# Schaltplan.net
KiCad netlist of a schematic drawn in EAGLE
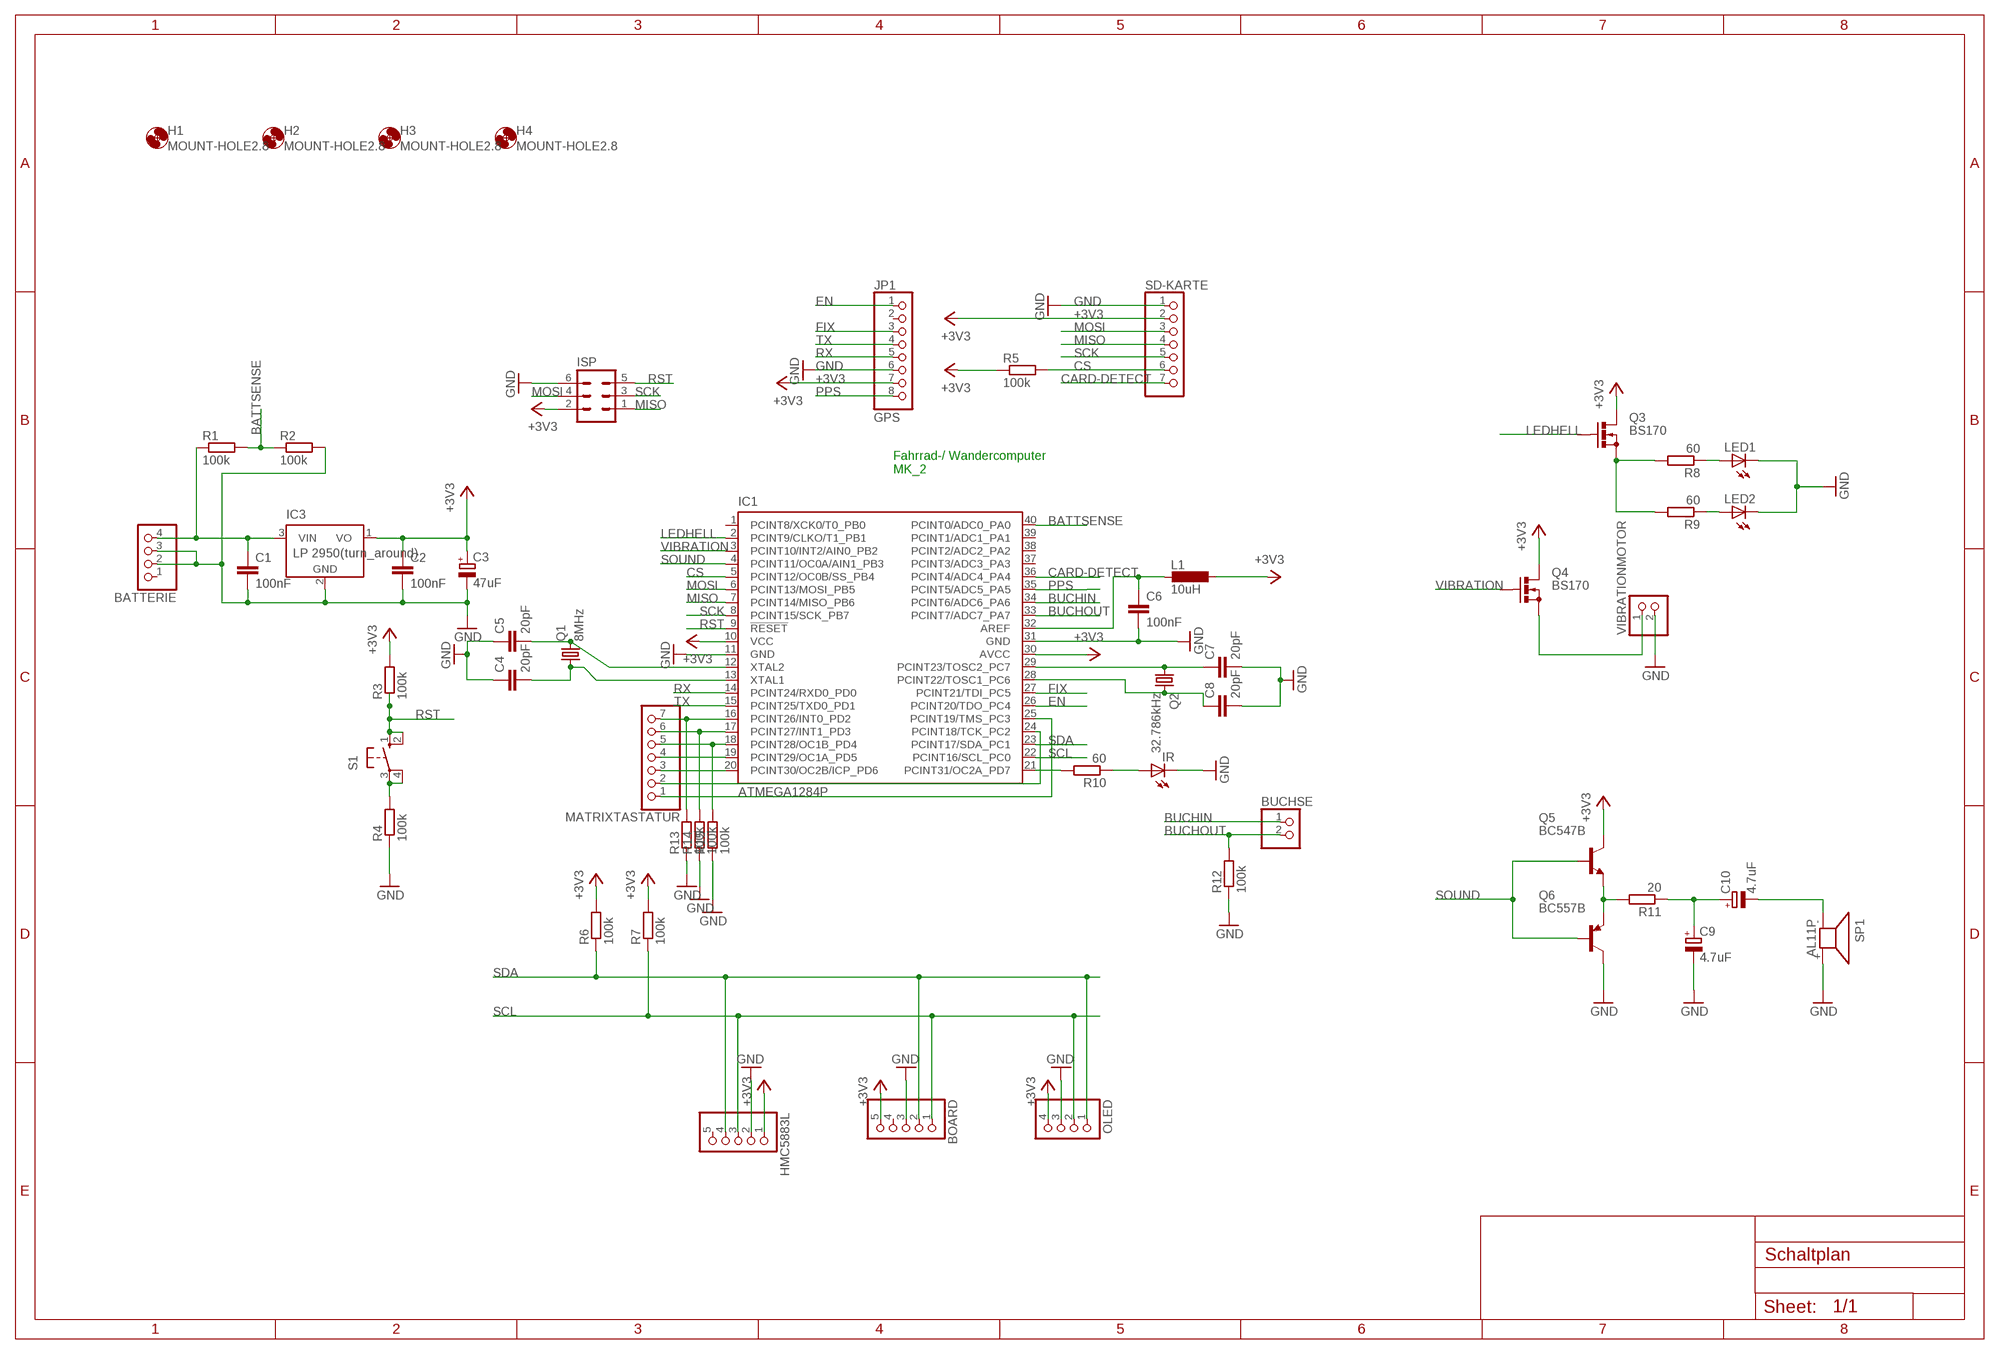
[diagram p0: schematic, sheet 1]

(export (version "E")
  (design (tool "Eeschema 10.0.6"))
  (components
    (comp (ref "BATTERIE")
      (value "PINHD-1X4")
      (footprint "eagle-import:1X04")
      (libsource (lib "eagle-import") (part "PINHD-1X4"))
    )
    (comp (ref "BOARD")
      (value "PINHD-1X5")
      (footprint "eagle-import:1X05")
      (libsource (lib "eagle-import") (part "PINHD-1X5"))
    )
    (comp (ref "BUCHSE")
      (value "PINHD-1X2")
      (footprint "eagle-import:1X02")
      (libsource (lib "eagle-import") (part "PINHD-1X2"))
    )
    (comp (ref "C1")
      (value "100nF")
      (footprint "eagle-import:C025-024X044")
      (libsource (lib "eagle-import") (part "C-EU025-024X044"))
    )
    (comp (ref "C2")
      (value "100nF")
      (footprint "eagle-import:C025-024X044")
      (libsource (lib "eagle-import") (part "C-EU025-024X044"))
    )
    (comp (ref "C3")
      (value "47uF")
      (footprint "eagle-import:E2,5-6")
      (libsource (lib "eagle-import") (part "CPOL-EUE2.5-6"))
    )
    (comp (ref "C4")
      (value "20pF")
      (footprint "eagle-import:C025-024X044")
      (libsource (lib "eagle-import") (part "C-EU025-024X044"))
    )
    (comp (ref "C5")
      (value "20pF")
      (footprint "eagle-import:C025-024X044")
      (libsource (lib "eagle-import") (part "C-EU025-024X044"))
    )
    (comp (ref "C6")
      (value "100nF")
      (footprint "eagle-import:C025-024X044")
      (libsource (lib "eagle-import") (part "C-EU025-024X044"))
    )
    (comp (ref "C7")
      (value "20pF")
      (footprint "eagle-import:C025-024X044")
      (libsource (lib "eagle-import") (part "C-EU025-024X044"))
    )
    (comp (ref "C8")
      (value "20pF")
      (footprint "eagle-import:C025-024X044")
      (libsource (lib "eagle-import") (part "C-EU025-024X044"))
    )
    (comp (ref "C9")
      (value "4.7uF")
      (footprint "eagle-import:E2,5-6")
      (libsource (lib "eagle-import") (part "CPOL-EUE2.5-6"))
    )
    (comp (ref "C10")
      (value "4.7uF")
      (footprint "eagle-import:E2,5-6")
      (libsource (lib "eagle-import") (part "CPOL-EUE2.5-6"))
    )
    (comp (ref "H1")
      (value "MOUNT-HOLE2.8")
      (footprint "eagle-import:2,8")
      (libsource (lib "eagle-import") (part "MOUNT-HOLE2.8"))
    )
    (comp (ref "H2")
      (value "MOUNT-HOLE2.8")
      (footprint "eagle-import:2,8")
      (libsource (lib "eagle-import") (part "MOUNT-HOLE2.8"))
    )
    (comp (ref "H3")
      (value "MOUNT-HOLE2.8")
      (footprint "eagle-import:2,8")
      (libsource (lib "eagle-import") (part "MOUNT-HOLE2.8"))
    )
    (comp (ref "H4")
      (value "MOUNT-HOLE2.8")
      (footprint "eagle-import:2,8")
      (libsource (lib "eagle-import") (part "MOUNT-HOLE2.8"))
    )
    (comp (ref "HMC5883L")
      (value "PINHD-1X5")
      (footprint "eagle-import:1X05")
      (libsource (lib "eagle-import") (part "PINHD-1X5"))
    )
    (comp (ref "IC1")
      (value "ATMEGA1284P")
      (footprint "eagle-import:DIL40")
      (fields (field (name "MPN") "ATMEGA644-20PU"))
      (libsource (lib "eagle-import") (part "ATMEGA644-PU20"))
    )
    (comp (ref "IC3")
      (value "LP 2950(turn_around)")
      (footprint "eagle-import:TO92")
      (fields (field (name "MF") "NATIONAL SEMICONDUCTOR") (field (name "MPN") "LM2936Z-3.0/NOPB"))
      (libsource (lib "eagle-import") (part "LM2936?Z-3.0"))
    )
    (comp (ref "IR")
      (value "LED3MM")
      (footprint "eagle-import:LED3MM")
      (libsource (lib "eagle-import") (part "LED3MM"))
    )
    (comp (ref "ISP")
      (value "ML6")
      (footprint "eagle-import:ML6")
      (libsource (lib "eagle-import") (part "ML6"))
    )
    (comp (ref "JP1")
      (value "GPS")
      (footprint "eagle-import:1X08")
      (libsource (lib "eagle-import") (part "PINHD-1X8"))
    )
    (comp (ref "L1")
      (value "10uH")
      (footprint "eagle-import:0207_10")
      (libsource (lib "eagle-import") (part "L-EU0207/10"))
    )
    (comp (ref "LED1")
      (value "LED5MM")
      (footprint "eagle-import:LED5MM")
      (libsource (lib "eagle-import") (part "LED5MM"))
    )
    (comp (ref "LED2")
      (value "LED5MM")
      (footprint "eagle-import:LED5MM")
      (libsource (lib "eagle-import") (part "LED5MM"))
    )
    (comp (ref "MATRIXTASTATUR")
      (value "PINHD-1X7")
      (footprint "eagle-import:1X07")
      (libsource (lib "eagle-import") (part "PINHD-1X7"))
    )
    (comp (ref "OLED")
      (value "PINHD-1X4")
      (footprint "eagle-import:1X04")
      (libsource (lib "eagle-import") (part "PINHD-1X4"))
    )
    (comp (ref "Q1")
      (value "8MHz")
      (footprint "eagle-import:HC49_S")
      (libsource (lib "eagle-import") (part "CRYSTALHC49S"))
    )
    (comp (ref "Q2")
      (value "32.786kHz")
      (footprint "eagle-import:TC26V")
      (libsource (lib "eagle-import") (part "CRYSTALTC26V"))
    )
    (comp (ref "Q3")
      (value "BS170")
      (footprint "eagle-import:SOT54E")
      (libsource (lib "eagle-import") (part "BS170"))
    )
    (comp (ref "Q4")
      (value "BS170")
      (footprint "eagle-import:SOT54E")
      (libsource (lib "eagle-import") (part "BS170"))
    )
    (comp (ref "Q5")
      (value "BC547B")
      (footprint "eagle-import:TO92")
      (libsource (lib "eagle-import") (part "BC547B"))
    )
    (comp (ref "Q6")
      (value "BC557B")
      (footprint "eagle-import:TO92-EBC")
      (libsource (lib "eagle-import") (part "BC557B"))
    )
    (comp (ref "R1")
      (value "100k")
      (footprint "eagle-import:0207_10")
      (libsource (lib "eagle-import") (part "R-EU_0207/10"))
    )
    (comp (ref "R2")
      (value "100k")
      (footprint "eagle-import:0207_10")
      (libsource (lib "eagle-import") (part "R-EU_0207/10"))
    )
    (comp (ref "R3")
      (value "100k")
      (footprint "eagle-import:0207_10")
      (libsource (lib "eagle-import") (part "R-EU_0207/10"))
    )
    (comp (ref "R4")
      (value "100k")
      (footprint "eagle-import:0207_10")
      (libsource (lib "eagle-import") (part "R-EU_0207/10"))
    )
    (comp (ref "R5")
      (value "100k")
      (footprint "eagle-import:0207_10")
      (libsource (lib "eagle-import") (part "R-EU_0207/10"))
    )
    (comp (ref "R6")
      (value "100k")
      (footprint "eagle-import:0207_10")
      (libsource (lib "eagle-import") (part "R-EU_0207/10"))
    )
    (comp (ref "R7")
      (value "100k")
      (footprint "eagle-import:0207_10")
      (libsource (lib "eagle-import") (part "R-EU_0207/10"))
    )
    (comp (ref "R8")
      (value "60")
      (footprint "eagle-import:0207_10")
      (libsource (lib "eagle-import") (part "R-EU_0207/10"))
    )
    (comp (ref "R9")
      (value "60")
      (footprint "eagle-import:0207_10")
      (libsource (lib "eagle-import") (part "R-EU_0207/10"))
    )
    (comp (ref "R10")
      (value "60")
      (footprint "eagle-import:0207_10")
      (libsource (lib "eagle-import") (part "R-EU_0207/10"))
    )
    (comp (ref "R11")
      (value "20")
      (footprint "eagle-import:0207_10")
      (libsource (lib "eagle-import") (part "R-EU_0207/10"))
    )
    (comp (ref "R12")
      (value "100k")
      (footprint "eagle-import:0207_10")
      (libsource (lib "eagle-import") (part "R-EU_0207/10"))
    )
    (comp (ref "R13")
      (value "100k")
      (footprint "eagle-import:0207_10")
      (libsource (lib "eagle-import") (part "R-EU_0207/10"))
    )
    (comp (ref "R14")
      (value "100k")
      (footprint "eagle-import:0207_10")
      (libsource (lib "eagle-import") (part "R-EU_0207/10"))
    )
    (comp (ref "R15")
      (value "100k")
      (footprint "eagle-import:0207_10")
      (libsource (lib "eagle-import") (part "R-EU_0207/10"))
    )
    (comp (ref "S1")
      (value "10-XX")
      (footprint "eagle-import:B3F-10XX")
      (fields (field (name "MPN") "B3F-1000"))
      (libsource (lib "eagle-import") (part "10-XX"))
    )
    (comp (ref "SD-KARTE")
      (value "PINHD-1X7")
      (footprint "eagle-import:1X07")
      (libsource (lib "eagle-import") (part "PINHD-1X7"))
    )
    (comp (ref "SP1")
      (value "AL11P")
      (footprint "eagle-import:AL11P")
      (libsource (lib "eagle-import") (part "AL11P"))
    )
    (comp (ref "VIBRATIONMOTOR")
      (value "PINHD-1X2")
      (footprint "eagle-import:1X02")
      (libsource (lib "eagle-import") (part "PINHD-1X2"))
    )
  )
  (nets
    (net (code "1") (name "+3V3") (class "Default")
      (node (ref "BOARD") (pin "5") (pinfunction "5_5") (pintype "passive"))
      (node (ref "C2") (pin "1") (pinfunction "1_1") (pintype "passive"))
      (node (ref "C3") (pin "+") (pinfunction "+_+") (pintype "passive"))
      (node (ref "HMC5883L") (pin "1") (pinfunction "1_1") (pintype "passive"))
      (node (ref "IC1") (pin "10") (pinfunction "VCC_10") (pintype "power_in"))
      (node (ref "IC1") (pin "30") (pinfunction "AVCC_30") (pintype "power_in"))
      (node (ref "IC3") (pin "1") (pinfunction "VO_1") (pintype "passive"))
      (node (ref "ISP") (pin "2") (pinfunction "2_2") (pintype "passive"))
      (node (ref "JP1") (pin "7") (pinfunction "7_7") (pintype "passive"))
      (node (ref "L1") (pin "1") (pinfunction "1_1") (pintype "passive"))
      (node (ref "OLED") (pin "4") (pinfunction "4_4") (pintype "passive"))
      (node (ref "Q3") (pin "D") (pinfunction "D_D") (pintype "passive"))
      (node (ref "Q4") (pin "D") (pinfunction "D_D") (pintype "passive"))
      (node (ref "Q5") (pin "3") (pinfunction "C_3") (pintype "passive"))
      (node (ref "R3") (pin "2") (pinfunction "2_2") (pintype "passive"))
      (node (ref "R5") (pin "1") (pinfunction "1_1") (pintype "passive"))
      (node (ref "R6") (pin "2") (pinfunction "2_2") (pintype "passive"))
      (node (ref "R7") (pin "2") (pinfunction "2_2") (pintype "passive"))
      (node (ref "SD-KARTE") (pin "2") (pinfunction "2_2") (pintype "passive"))
    )
    (net (code "2") (name "/BATTSENSE") (class "Default")
      (node (ref "IC1") (pin "40") (pinfunction "PCINT0/ADC0_PA0_40") (pintype "bidirectional"))
      (node (ref "R1") (pin "2") (pinfunction "2_2") (pintype "passive"))
      (node (ref "R2") (pin "1") (pinfunction "1_1") (pintype "passive"))
    )
    (net (code "3") (name "/BUCHIN") (class "Default")
      (node (ref "BUCHSE") (pin "1") (pinfunction "1_1") (pintype "passive"))
      (node (ref "IC1") (pin "34") (pinfunction "PCINT6/ADC6_PA6_34") (pintype "bidirectional"))
    )
    (net (code "4") (name "/BUCHOUT") (class "Default")
      (node (ref "BUCHSE") (pin "2") (pinfunction "2_2") (pintype "passive"))
      (node (ref "IC1") (pin "33") (pinfunction "PCINT7/ADC7_PA7_33") (pintype "bidirectional"))
      (node (ref "R12") (pin "2") (pinfunction "2_2") (pintype "passive"))
    )
    (net (code "5") (name "/CARD-DETECT") (class "Default")
      (node (ref "IC1") (pin "36") (pinfunction "PCINT4/ADC4_PA4_36") (pintype "bidirectional"))
      (node (ref "SD-KARTE") (pin "7") (pinfunction "7_7") (pintype "passive"))
    )
    (net (code "6") (name "/CS") (class "Default")
      (node (ref "IC1") (pin "5") (pinfunction "PCINT12/OC0B/SS_PB4_5") (pintype "bidirectional"))
      (node (ref "R5") (pin "2") (pinfunction "2_2") (pintype "passive"))
      (node (ref "SD-KARTE") (pin "6") (pinfunction "6_6") (pintype "passive"))
    )
    (net (code "7") (name "/EN") (class "Default")
      (node (ref "IC1") (pin "26") (pinfunction "PCINT20/TDO_PC4_26") (pintype "bidirectional"))
      (node (ref "JP1") (pin "1") (pinfunction "1_1") (pintype "passive"))
    )
    (net (code "8") (name "/FIX") (class "Default")
      (node (ref "IC1") (pin "27") (pinfunction "PCINT21/TDI_PC5_27") (pintype "bidirectional"))
      (node (ref "JP1") (pin "3") (pinfunction "3_3") (pintype "passive"))
    )
    (net (code "9") (name "/LEDHELL") (class "Default")
      (node (ref "IC1") (pin "2") (pinfunction "PCINT9/CLKO/T1_PB1_2") (pintype "bidirectional"))
      (node (ref "Q3") (pin "G") (pinfunction "G_G") (pintype "passive"))
    )
    (net (code "10") (name "/MISO") (class "Default")
      (node (ref "IC1") (pin "7") (pinfunction "PCINT14/MISO_PB6_7") (pintype "bidirectional"))
      (node (ref "ISP") (pin "1") (pinfunction "1_1") (pintype "passive"))
      (node (ref "SD-KARTE") (pin "4") (pinfunction "4_4") (pintype "passive"))
    )
    (net (code "11") (name "/MOSI") (class "Default")
      (node (ref "IC1") (pin "6") (pinfunction "PCINT13/MOSI_PB5_6") (pintype "bidirectional"))
      (node (ref "ISP") (pin "4") (pinfunction "4_4") (pintype "passive"))
      (node (ref "SD-KARTE") (pin "3") (pinfunction "3_3") (pintype "passive"))
    )
    (net (code "12") (name "/PPS") (class "Default")
      (node (ref "IC1") (pin "35") (pinfunction "PCINT5/ADC5_PA5_35") (pintype "bidirectional"))
      (node (ref "JP1") (pin "8") (pinfunction "8_8") (pintype "passive"))
    )
    (net (code "13") (name "/RST") (class "Default")
      (node (ref "IC1") (pin "9") (pinfunction "~{RESET}_9") (pintype "input"))
      (node (ref "ISP") (pin "5") (pinfunction "5_5") (pintype "passive"))
      (node (ref "R3") (pin "1") (pinfunction "1_1") (pintype "passive"))
      (node (ref "S1") (pin "1") (pinfunction "S_1") (pintype "passive"))
      (node (ref "S1") (pin "2") (pinfunction "S1_2") (pintype "passive"))
    )
    (net (code "14") (name "/RX") (class "Default")
      (node (ref "IC1") (pin "14") (pinfunction "PCINT24/RXD0_PD0_14") (pintype "bidirectional"))
      (node (ref "JP1") (pin "5") (pinfunction "5_5") (pintype "passive"))
    )
    (net (code "15") (name "/SCK") (class "Default")
      (node (ref "IC1") (pin "8") (pinfunction "PCINT15/SCK_PB7_8") (pintype "bidirectional"))
      (node (ref "ISP") (pin "3") (pinfunction "3_3") (pintype "passive"))
      (node (ref "SD-KARTE") (pin "5") (pinfunction "5_5") (pintype "passive"))
    )
    (net (code "16") (name "/SCL") (class "Default")
      (node (ref "BOARD") (pin "1") (pinfunction "1_1") (pintype "passive"))
      (node (ref "HMC5883L") (pin "3") (pinfunction "3_3") (pintype "passive"))
      (node (ref "IC1") (pin "22") (pinfunction "PCINT16/SCL_PC0_22") (pintype "bidirectional"))
      (node (ref "OLED") (pin "2") (pinfunction "2_2") (pintype "passive"))
      (node (ref "R7") (pin "1") (pinfunction "1_1") (pintype "passive"))
    )
    (net (code "17") (name "/SDA") (class "Default")
      (node (ref "BOARD") (pin "2") (pinfunction "2_2") (pintype "passive"))
      (node (ref "HMC5883L") (pin "4") (pinfunction "4_4") (pintype "passive"))
      (node (ref "IC1") (pin "23") (pinfunction "PCINT17/SDA_PC1_23") (pintype "bidirectional"))
      (node (ref "OLED") (pin "1") (pinfunction "1_1") (pintype "passive"))
      (node (ref "R6") (pin "1") (pinfunction "1_1") (pintype "passive"))
    )
    (net (code "18") (name "/SOUND") (class "Default")
      (node (ref "IC1") (pin "4") (pinfunction "PCINT11/OC0A/AIN1_PB3_4") (pintype "bidirectional"))
      (node (ref "Q5") (pin "2") (pinfunction "B_2") (pintype "passive"))
      (node (ref "Q6") (pin "B") (pinfunction "B_B") (pintype "passive"))
    )
    (net (code "19") (name "/TX") (class "Default")
      (node (ref "IC1") (pin "15") (pinfunction "PCINT25/TXD0_PD1_15") (pintype "bidirectional"))
      (node (ref "JP1") (pin "4") (pinfunction "4_4") (pintype "passive"))
    )
    (net (code "20") (name "/VIBRATION") (class "Default")
      (node (ref "IC1") (pin "3") (pinfunction "PCINT10/INT2/AIN0_PB2_3") (pintype "bidirectional"))
      (node (ref "Q4") (pin "G") (pinfunction "G_G") (pintype "passive"))
    )
    (net (code "21") (name "GND") (class "Default")
      (node (ref "BATTERIE") (pin "2") (pinfunction "2_2") (pintype "passive"))
      (node (ref "BATTERIE") (pin "3") (pinfunction "3_3") (pintype "passive"))
      (node (ref "BOARD") (pin "3") (pinfunction "3_3") (pintype "passive"))
      (node (ref "C1") (pin "2") (pinfunction "2_2") (pintype "passive"))
      (node (ref "C2") (pin "2") (pinfunction "2_2") (pintype "passive"))
      (node (ref "C3") (pin "-") (pinfunction "-_-") (pintype "passive"))
      (node (ref "C4") (pin "1") (pinfunction "1_1") (pintype "passive"))
      (node (ref "C5") (pin "1") (pinfunction "1_1") (pintype "passive"))
      (node (ref "C6") (pin "2") (pinfunction "2_2") (pintype "passive"))
      (node (ref "C7") (pin "2") (pinfunction "2_2") (pintype "passive"))
      (node (ref "C8") (pin "2") (pinfunction "2_2") (pintype "passive"))
      (node (ref "C9") (pin "-") (pinfunction "-_-") (pintype "passive"))
      (node (ref "HMC5883L") (pin "2") (pinfunction "2_2") (pintype "passive"))
      (node (ref "IC1") (pin "11") (pinfunction "GND_11") (pintype "power_in"))
      (node (ref "IC1") (pin "31") (pinfunction "GND_31") (pintype "power_in"))
      (node (ref "IC3") (pin "2") (pinfunction "GND_2") (pintype "passive"))
      (node (ref "IR") (pin "K") (pinfunction "C_K") (pintype "passive"))
      (node (ref "ISP") (pin "6") (pinfunction "6_6") (pintype "passive"))
      (node (ref "JP1") (pin "6") (pinfunction "6_6") (pintype "passive"))
      (node (ref "LED1") (pin "K") (pinfunction "C_K") (pintype "passive"))
      (node (ref "LED2") (pin "K") (pinfunction "C_K") (pintype "passive"))
      (node (ref "OLED") (pin "3") (pinfunction "3_3") (pintype "passive"))
      (node (ref "Q6") (pin "C") (pinfunction "C_C") (pintype "passive"))
      (node (ref "R12") (pin "1") (pinfunction "1_1") (pintype "passive"))
      (node (ref "R13") (pin "1") (pinfunction "1_1") (pintype "passive"))
      (node (ref "R14") (pin "1") (pinfunction "1_1") (pintype "passive"))
      (node (ref "R15") (pin "1") (pinfunction "1_1") (pintype "passive"))
      (node (ref "R2") (pin "2") (pinfunction "2_2") (pintype "passive"))
      (node (ref "R4") (pin "1") (pinfunction "1_1") (pintype "passive"))
      (node (ref "SD-KARTE") (pin "1") (pinfunction "1_1") (pintype "passive"))
      (node (ref "SP1") (pin "+") (pinfunction "2_+") (pintype "passive"))
      (node (ref "VIBRATIONMOTOR") (pin "2") (pinfunction "2_2") (pintype "passive"))
    )
    (net (code "22") (name "Net-(C10-Pad+)") (class "Default")
      (node (ref "C10") (pin "+") (pinfunction "+_+") (pintype "passive"))
      (node (ref "C9") (pin "+") (pinfunction "+_+") (pintype "passive"))
      (node (ref "R11") (pin "1") (pinfunction "1_1") (pintype "passive"))
    )
    (net (code "23") (name "Net-(IC1-AREF)") (class "Default")
      (node (ref "C6") (pin "1") (pinfunction "1_1") (pintype "passive"))
      (node (ref "IC1") (pin "32") (pinfunction "AREF_32") (pintype "passive"))
      (node (ref "L1") (pin "2") (pinfunction "2_2") (pintype "passive"))
    )
    (net (code "24") (name "Net-(IC1-PCINT18{slash}TCK_PC2)") (class "Default")
      (node (ref "IC1") (pin "24") (pinfunction "PCINT18/TCK_PC2_24") (pintype "bidirectional"))
      (node (ref "MATRIXTASTATUR") (pin "2") (pinfunction "2_2") (pintype "passive"))
    )
    (net (code "25") (name "Net-(IC1-PCINT19{slash}TMS_PC3)") (class "Default")
      (node (ref "IC1") (pin "25") (pinfunction "PCINT19/TMS_PC3_25") (pintype "bidirectional"))
      (node (ref "MATRIXTASTATUR") (pin "1") (pinfunction "1_1") (pintype "passive"))
    )
    (net (code "26") (name "Net-(IC1-PCINT22{slash}TOSC1_PC6)") (class "Default")
      (node (ref "C8") (pin "1") (pinfunction "1_1") (pintype "passive"))
      (node (ref "IC1") (pin "28") (pinfunction "PCINT22/TOSC1_PC6_28") (pintype "bidirectional"))
      (node (ref "Q2") (pin "2") (pinfunction "2_2") (pintype "passive"))
    )
    (net (code "27") (name "Net-(IC1-PCINT23{slash}TOSC2_PC7)") (class "Default")
      (node (ref "C7") (pin "1") (pinfunction "1_1") (pintype "passive"))
      (node (ref "IC1") (pin "29") (pinfunction "PCINT23/TOSC2_PC7_29") (pintype "bidirectional"))
      (node (ref "Q2") (pin "1") (pinfunction "1_1") (pintype "passive"))
    )
    (net (code "28") (name "Net-(IC1-PCINT26{slash}INT0_PD2)") (class "Default")
      (node (ref "IC1") (pin "16") (pinfunction "PCINT26/INT0_PD2_16") (pintype "bidirectional"))
      (node (ref "MATRIXTASTATUR") (pin "7") (pinfunction "7_7") (pintype "passive"))
      (node (ref "R13") (pin "2") (pinfunction "2_2") (pintype "passive"))
    )
    (net (code "29") (name "Net-(IC1-PCINT27{slash}INT1_PD3)") (class "Default")
      (node (ref "IC1") (pin "17") (pinfunction "PCINT27/INT1_PD3_17") (pintype "bidirectional"))
      (node (ref "MATRIXTASTATUR") (pin "6") (pinfunction "6_6") (pintype "passive"))
      (node (ref "R14") (pin "2") (pinfunction "2_2") (pintype "passive"))
    )
    (net (code "30") (name "Net-(IC1-PCINT28{slash}OC1B_PD4)") (class "Default")
      (node (ref "IC1") (pin "18") (pinfunction "PCINT28/OC1B_PD4_18") (pintype "bidirectional"))
      (node (ref "MATRIXTASTATUR") (pin "5") (pinfunction "5_5") (pintype "passive"))
      (node (ref "R15") (pin "2") (pinfunction "2_2") (pintype "passive"))
    )
    (net (code "31") (name "Net-(IC1-PCINT29{slash}OC1A_PD5)") (class "Default")
      (node (ref "IC1") (pin "19") (pinfunction "PCINT29/OC1A_PD5_19") (pintype "bidirectional"))
      (node (ref "MATRIXTASTATUR") (pin "4") (pinfunction "4_4") (pintype "passive"))
    )
    (net (code "32") (name "Net-(IC1-PCINT30{slash}OC2B{slash}ICP_PD6)") (class "Default")
      (node (ref "IC1") (pin "20") (pinfunction "PCINT30/OC2B/ICP_PD6_20") (pintype "bidirectional"))
      (node (ref "MATRIXTASTATUR") (pin "3") (pinfunction "3_3") (pintype "passive"))
    )
    (net (code "33") (name "Net-(IC1-PCINT31{slash}OC2A_PD7)") (class "Default")
      (node (ref "IC1") (pin "21") (pinfunction "PCINT31/OC2A_PD7_21") (pintype "bidirectional"))
      (node (ref "R10") (pin "2") (pinfunction "2_2") (pintype "passive"))
    )
    (net (code "34") (name "Net-(IC1-XTAL1)") (class "Default")
      (node (ref "C4") (pin "2") (pinfunction "2_2") (pintype "passive"))
      (node (ref "IC1") (pin "13") (pinfunction "XTAL1_13") (pintype "input"))
      (node (ref "Q1") (pin "1") (pinfunction "1_1") (pintype "passive"))
    )
    (net (code "35") (name "Net-(IC1-XTAL2)") (class "Default")
      (node (ref "C5") (pin "2") (pinfunction "2_2") (pintype "passive"))
      (node (ref "IC1") (pin "12") (pinfunction "XTAL2_12") (pintype "output"))
      (node (ref "Q1") (pin "2") (pinfunction "2_2") (pintype "passive"))
    )
    (net (code "36") (name "Net-(IC3-VIN)") (class "Default")
      (node (ref "BATTERIE") (pin "4") (pinfunction "4_4") (pintype "passive"))
      (node (ref "C1") (pin "1") (pinfunction "1_1") (pintype "passive"))
      (node (ref "IC3") (pin "3") (pinfunction "VIN_3") (pintype "input"))
      (node (ref "R1") (pin "1") (pinfunction "1_1") (pintype "passive"))
    )
    (net (code "37") (name "Net-(IR-PadA)") (class "Default")
      (node (ref "IR") (pin "A") (pinfunction "A_A") (pintype "passive"))
      (node (ref "R10") (pin "1") (pinfunction "1_1") (pintype "passive"))
    )
    (net (code "38") (name "Net-(LED1-PadA)") (class "Default")
      (node (ref "LED1") (pin "A") (pinfunction "A_A") (pintype "passive"))
      (node (ref "R8") (pin "1") (pinfunction "1_1") (pintype "passive"))
    )
    (net (code "39") (name "Net-(LED2-PadA)") (class "Default")
      (node (ref "LED2") (pin "A") (pinfunction "A_A") (pintype "passive"))
      (node (ref "R9") (pin "1") (pinfunction "1_1") (pintype "passive"))
    )
    (net (code "40") (name "Net-(Q3-PadS)") (class "Default")
      (node (ref "Q3") (pin "S") (pinfunction "S_S") (pintype "passive"))
      (node (ref "R8") (pin "2") (pinfunction "2_2") (pintype "passive"))
      (node (ref "R9") (pin "2") (pinfunction "2_2") (pintype "passive"))
    )
    (net (code "41") (name "Net-(Q4-PadS)") (class "Default")
      (node (ref "Q4") (pin "S") (pinfunction "S_S") (pintype "passive"))
      (node (ref "VIBRATIONMOTOR") (pin "1") (pinfunction "1_1") (pintype "passive"))
    )
    (net (code "42") (name "Net-(Q5-E)") (class "Default")
      (node (ref "Q5") (pin "1") (pinfunction "E_1") (pintype "passive"))
      (node (ref "Q6") (pin "E") (pinfunction "E_E") (pintype "passive"))
      (node (ref "R11") (pin "2") (pinfunction "2_2") (pintype "passive"))
    )
    (net (code "43") (name "Net-(S1-P)") (class "Default")
      (node (ref "R4") (pin "2") (pinfunction "2_2") (pintype "passive"))
      (node (ref "S1") (pin "3") (pinfunction "P_3") (pintype "passive"))
      (node (ref "S1") (pin "4") (pinfunction "P1_4") (pintype "passive"))
    )
    (net (code "44") (name "Net-(SP1-1)") (class "Default")
      (node (ref "C10") (pin "-") (pinfunction "-_-") (pintype "passive"))
      (node (ref "SP1") (pin "-") (pinfunction "1_-") (pintype "passive"))
    )
    (net (code "45") (name "unconnected-(BATTERIE-Pad1)") (class "Default")
      (node (ref "BATTERIE") (pin "1") (pinfunction "1_1") (pintype "passive"))
    )
    (net (code "46") (name "unconnected-(BOARD-Pad4)") (class "Default")
      (node (ref "BOARD") (pin "4") (pinfunction "4_4") (pintype "passive"))
    )
    (net (code "47") (name "unconnected-(HMC5883L-Pad5)") (class "Default")
      (node (ref "HMC5883L") (pin "5") (pinfunction "5_5") (pintype "passive"))
    )
    (net (code "48") (name "unconnected-(IC1-PCINT1{slash}ADC1_PA1-Pad39)") (class "Default")
      (node (ref "IC1") (pin "39") (pinfunction "PCINT1/ADC1_PA1_39") (pintype "bidirectional"))
    )
    (net (code "49") (name "unconnected-(IC1-PCINT2{slash}ADC2_PA2-Pad38)") (class "Default")
      (node (ref "IC1") (pin "38") (pinfunction "PCINT2/ADC2_PA2_38") (pintype "bidirectional"))
    )
    (net (code "50") (name "unconnected-(IC1-PCINT3{slash}ADC3_PA3-Pad37)") (class "Default")
      (node (ref "IC1") (pin "37") (pinfunction "PCINT3/ADC3_PA3_37") (pintype "bidirectional"))
    )
    (net (code "51") (name "unconnected-(IC1-PCINT8{slash}XCK0{slash}T0_PB0-Pad1)") (class "Default")
      (node (ref "IC1") (pin "1") (pinfunction "PCINT8/XCK0/T0_PB0_1") (pintype "bidirectional"))
    )
    (net (code "52") (name "unconnected-(JP1-Pad2)") (class "Default")
      (node (ref "JP1") (pin "2") (pinfunction "2_2") (pintype "passive"))
    )
  )
)
